# RatGDO.net
KiCad netlist of a schematic drawn in EAGLE
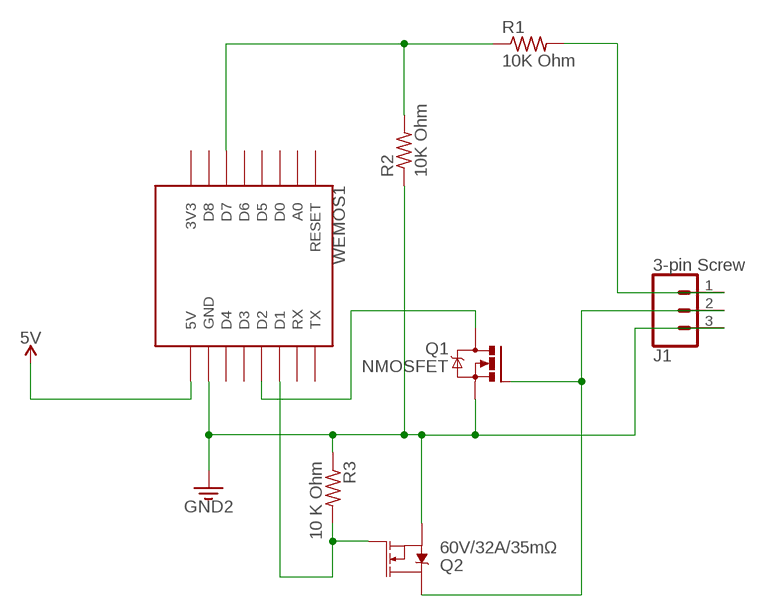
[diagram p0: schematic, sheet 1]

(export (version "E")
  (design (tool "Eeschema 10.0.6"))
  (components
    (comp (ref "J1")
      (value "3-pin Screw")
      (footprint "eagle-import:SCREWTERMINAL-3.5MM-3")
      (libsource (lib "eagle-import") (part "CONN_03SCREW"))
    )
    (comp (ref "Q1")
      (value "NMOSFET")
      (footprint "eagle-import:TO92")
      (libsource (lib "eagle-import") (part "NMOSFETTO92-DGS_"))
    )
    (comp (ref "Q2")
      (value "60V/32A/35mΩ")
      (footprint "eagle-import:TO220V")
      (libsource (lib "eagle-import") (part "MOSFET-NCH-FQP30N06L"))
    )
    (comp (ref "R1")
      (value "10K Ohm")
      (footprint "eagle-import:0309_12")
      (libsource (lib "eagle-import") (part "R-US_0309/12"))
    )
    (comp (ref "R2")
      (value "10K Ohm")
      (footprint "eagle-import:0309_12")
      (libsource (lib "eagle-import") (part "R-US_0309/12"))
    )
    (comp (ref "R3")
      (value "10 K Ohm")
      (footprint "eagle-import:0309_12")
      (libsource (lib "eagle-import") (part "R-US_0309/12"))
    )
    (comp (ref "WEMOS1")
      (value "WEMOS-D1-MINI")
      (footprint "eagle-import:WEMOS-D1-MINI")
      (libsource (lib "eagle-import") (part "WEMOS-D1-MINI"))
    )
  )
  (nets
    (net (code "1") (name "5V") (class "Default")
      (node (ref "WEMOS1") (pin "5V") (pinfunction "5V_5V") (pintype "bidirectional"))
    )
    (net (code "2") (name "GND2") (class "Default")
      (node (ref "J1") (pin "3") (pinfunction "3_3") (pintype "passive"))
      (node (ref "Q1") (pin "3") (pinfunction "S_3") (pintype "passive"))
      (node (ref "Q2") (pin "3") (pinfunction "S_3") (pintype "bidirectional"))
      (node (ref "R2") (pin "1") (pinfunction "1_1") (pintype "passive"))
      (node (ref "R3") (pin "1") (pinfunction "1_1") (pintype "passive"))
      (node (ref "WEMOS1") (pin "GND") (pinfunction "GND_GND") (pintype "bidirectional"))
    )
    (net (code "3") (name "Net-(J1-Pad1)") (class "Default")
      (node (ref "J1") (pin "1") (pinfunction "1_1") (pintype "passive"))
      (node (ref "R1") (pin "2") (pinfunction "2_2") (pintype "passive"))
    )
    (net (code "4") (name "Net-(Q1-D)") (class "Default")
      (node (ref "Q1") (pin "1") (pinfunction "D_1") (pintype "passive"))
      (node (ref "WEMOS1") (pin "D2") (pinfunction "D2_D2") (pintype "bidirectional"))
    )
    (net (code "5") (name "Net-(Q1-G)") (class "Default")
      (node (ref "J1") (pin "2") (pinfunction "2_2") (pintype "passive"))
      (node (ref "Q1") (pin "2") (pinfunction "G_2") (pintype "passive"))
      (node (ref "Q2") (pin "2") (pinfunction "D_2") (pintype "bidirectional"))
    )
    (net (code "6") (name "Net-(Q2-G)") (class "Default")
      (node (ref "Q2") (pin "1") (pinfunction "G_1") (pintype "bidirectional"))
      (node (ref "R3") (pin "2") (pinfunction "2_2") (pintype "passive"))
      (node (ref "WEMOS1") (pin "D1") (pinfunction "D1_D1") (pintype "bidirectional"))
    )
    (net (code "7") (name "Net-(R1-Pad1)") (class "Default")
      (node (ref "R1") (pin "1") (pinfunction "1_1") (pintype "passive"))
      (node (ref "R2") (pin "2") (pinfunction "2_2") (pintype "passive"))
      (node (ref "WEMOS1") (pin "D7") (pinfunction "D7_D7") (pintype "bidirectional"))
    )
    (net (code "8") (name "unconnected-(WEMOS1-Pad3V3)") (class "Default")
      (node (ref "WEMOS1") (pin "3V3") (pinfunction "3V3_3V3") (pintype "bidirectional"))
    )
    (net (code "9") (name "unconnected-(WEMOS1-PadA0)") (class "Default")
      (node (ref "WEMOS1") (pin "A0") (pinfunction "A0_A0") (pintype "bidirectional"))
    )
    (net (code "10") (name "unconnected-(WEMOS1-PadD0)") (class "Default")
      (node (ref "WEMOS1") (pin "D0") (pinfunction "D0_D0") (pintype "bidirectional"))
    )
    (net (code "11") (name "unconnected-(WEMOS1-PadD3)") (class "Default")
      (node (ref "WEMOS1") (pin "D3") (pinfunction "D3_D3") (pintype "bidirectional"))
    )
    (net (code "12") (name "unconnected-(WEMOS1-PadD4)") (class "Default")
      (node (ref "WEMOS1") (pin "D4") (pinfunction "D4_D4") (pintype "bidirectional"))
    )
    (net (code "13") (name "unconnected-(WEMOS1-PadD5)") (class "Default")
      (node (ref "WEMOS1") (pin "D5") (pinfunction "D5_D5") (pintype "bidirectional"))
    )
    (net (code "14") (name "unconnected-(WEMOS1-PadD6)") (class "Default")
      (node (ref "WEMOS1") (pin "D6") (pinfunction "D6_D6") (pintype "bidirectional"))
    )
    (net (code "15") (name "unconnected-(WEMOS1-PadD8)") (class "Default")
      (node (ref "WEMOS1") (pin "D8") (pinfunction "D8_D8") (pintype "bidirectional"))
    )
    (net (code "16") (name "unconnected-(WEMOS1-PadRESET)") (class "Default")
      (node (ref "WEMOS1") (pin "RESET") (pinfunction "RESET_RESET") (pintype "bidirectional"))
    )
    (net (code "17") (name "unconnected-(WEMOS1-PadRX)") (class "Default")
      (node (ref "WEMOS1") (pin "RX") (pinfunction "RX_RX") (pintype "bidirectional"))
    )
    (net (code "18") (name "unconnected-(WEMOS1-PadTX)") (class "Default")
      (node (ref "WEMOS1") (pin "TX") (pinfunction "TX_TX") (pintype "bidirectional"))
    )
  )
)
